# Sheet_CL-RMS-01.net
KiCad netlist of a schematic drawn in Altium Designer
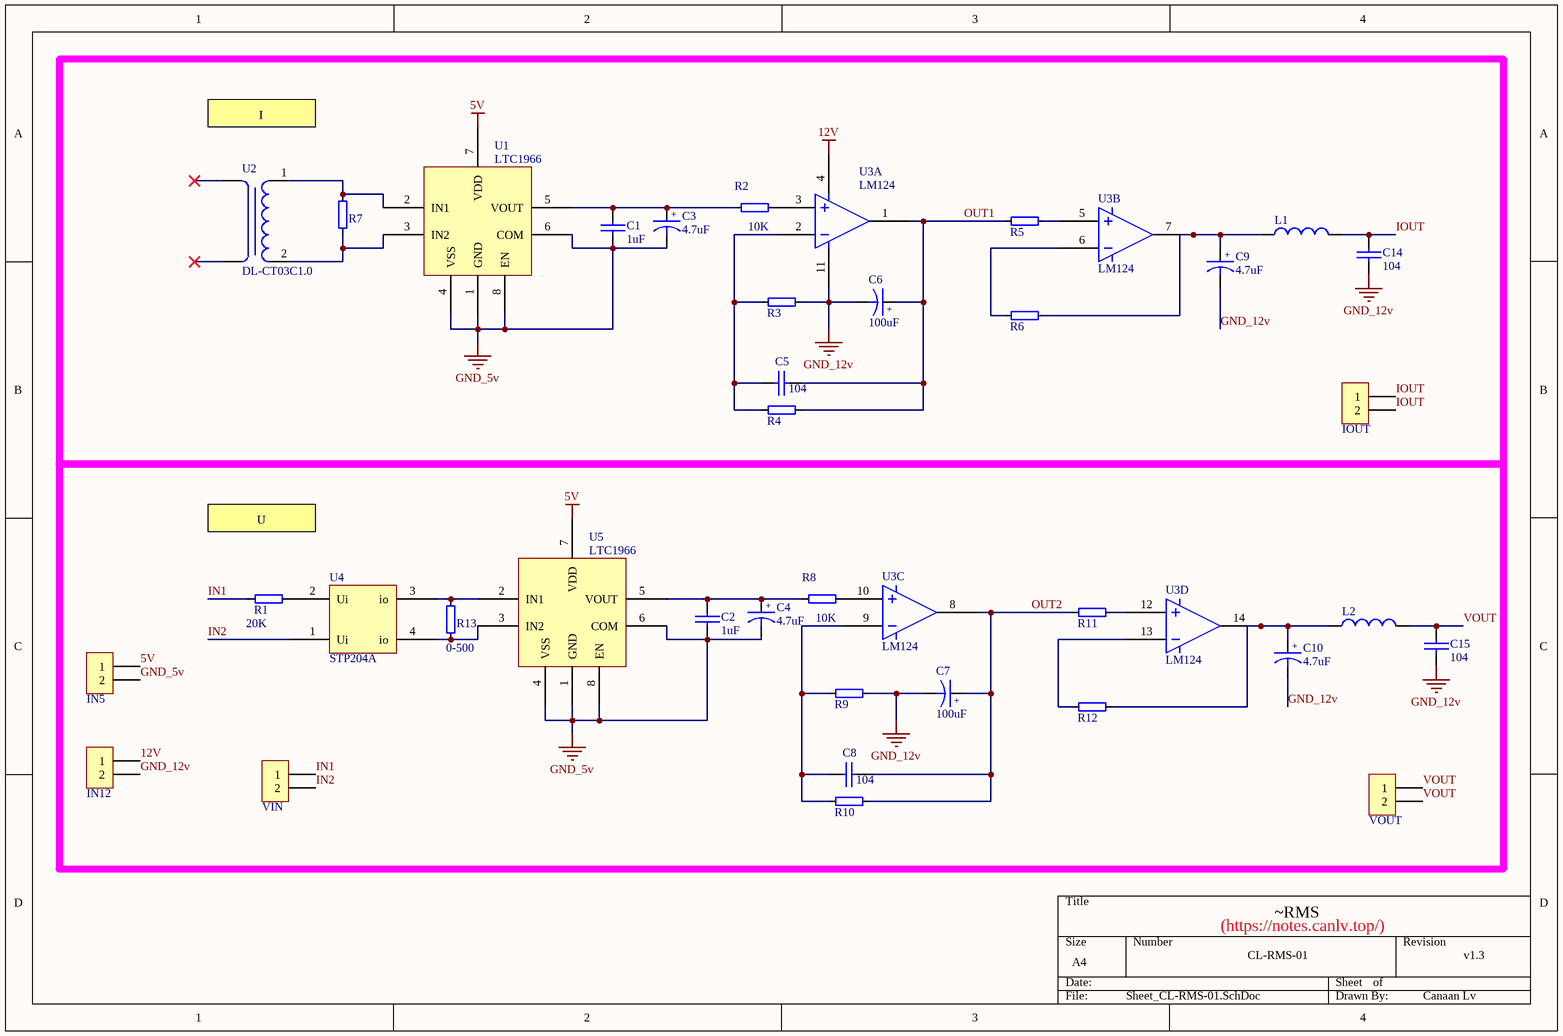
[diagram p0: Sheet_CL-RMS-01.SchDoc]

(export (version "E")
  (design (tool "Eeschema 10.0.6"))
  (components
    (comp (ref "C1")
      (value "普通电容")
      (footprint "C0805")
      (description "Capacitor")
      (fields (field (name "ALTIUM_UNNAMED_1") "1uF"))
      (libsource (lib "电容") (part "普通电容"))
    )
    (comp (ref "C2")
      (value "普通电容")
      (footprint "C0805")
      (description "Capacitor")
      (fields (field (name "ALTIUM_UNNAMED_1") "1uF"))
      (libsource (lib "电容") (part "普通电容"))
    )
    (comp (ref "C3")
      (value "电解电容")
      (footprint "CZ0.50/25V47U")
      (description "Capacitor")
      (fields (field (name "ALTIUM_UNNAMED_1") "4.7uF"))
      (libsource (lib "电容") (part "电解电容"))
    )
    (comp (ref "C4")
      (value "电解电容")
      (footprint "CZ0.50/25V47U")
      (description "Capacitor")
      (fields (field (name "ALTIUM_UNNAMED_1") "4.7uF"))
      (libsource (lib "电容") (part "电解电容"))
    )
    (comp (ref "C5")
      (value "普通电容")
      (footprint "C0805")
      (description "Capacitor")
      (fields (field (name "ALTIUM_UNNAMED_1") "104"))
      (libsource (lib "电容") (part "普通电容"))
    )
    (comp (ref "C6")
      (value "电解电容")
      (footprint "CZ0.50/25V47U")
      (description "Capacitor")
      (fields (field (name "ALTIUM_UNNAMED_1") "100uF"))
      (libsource (lib "电容") (part "电解电容"))
    )
    (comp (ref "C7")
      (value "电解电容")
      (footprint "CZ0.50/25V47U")
      (description "Capacitor")
      (fields (field (name "ALTIUM_UNNAMED_1") "100uF"))
      (libsource (lib "电容") (part "电解电容"))
    )
    (comp (ref "C8")
      (value "普通电容")
      (footprint "C0805")
      (description "Capacitor")
      (fields (field (name "ALTIUM_UNNAMED_1") "104"))
      (libsource (lib "电容") (part "普通电容"))
    )
    (comp (ref "C9")
      (value "电解电容")
      (footprint "CZ0.50/25V47U")
      (description "Capacitor")
      (fields (field (name "ALTIUM_UNNAMED_1") "4.7uF"))
      (libsource (lib "电容") (part "电解电容"))
    )
    (comp (ref "C10")
      (value "电解电容")
      (footprint "CZ0.50/25V47U")
      (description "Capacitor")
      (fields (field (name "ALTIUM_UNNAMED_1") "4.7uF"))
      (libsource (lib "电容") (part "电解电容"))
    )
    (comp (ref "C14")
      (value "普通电容")
      (footprint "C0805")
      (description "Capacitor")
      (fields (field (name "ALTIUM_UNNAMED_1") "104"))
      (libsource (lib "电容") (part "普通电容"))
    )
    (comp (ref "C15")
      (value "普通电容")
      (footprint "C0805")
      (description "Capacitor")
      (fields (field (name "ALTIUM_UNNAMED_1") "104"))
      (libsource (lib "电容") (part "普通电容"))
    )
    (comp (ref "IN5")
      (value "CON2")
      (footprint "P2")
      (description "Connector")
      (libsource (lib "插件") (part "CON2"))
    )
    (comp (ref "IN12")
      (value "CON2")
      (footprint "P2")
      (description "Connector")
      (libsource (lib "插件") (part "CON2"))
    )
    (comp (ref "IOUT")
      (value "CON2")
      (footprint "P2")
      (description "Connector")
      (libsource (lib "插件") (part "CON2"))
    )
    (comp (ref "L1") (value "~") (footprint "L1206") (libsource (lib "电感") (part "贴片电感")))
    (comp (ref "L2") (value "~") (footprint "L1206") (libsource (lib "电感") (part "贴片电感")))
    (comp (ref "R1")
      (value "RES")
      (footprint "W1")
      (fields (field (name "ALTIUM_UNNAMED_1") "20K"))
      (libsource (lib "电阻") (part "RES"))
    )
    (comp (ref "R2")
      (value "RES")
      (footprint "C0805")
      (fields (field (name "ALTIUM_UNNAMED_1") "10K"))
      (libsource (lib "电阻") (part "RES"))
    )
    (comp (ref "R3") (value "RES") (footprint "C0805") (libsource (lib "电阻") (part "RES")))
    (comp (ref "R4") (value "RES") (footprint "W1") (libsource (lib "电阻") (part "RES")))
    (comp (ref "R5") (value "RES") (footprint "C0805") (libsource (lib "电阻") (part "RES")))
    (comp (ref "R6") (value "RES") (footprint "C0805") (libsource (lib "电阻") (part "RES")))
    (comp (ref "R7") (value "RES") (footprint "W1") (libsource (lib "电阻") (part "RES")))
    (comp (ref "R8")
      (value "RES")
      (footprint "C0805")
      (fields (field (name "ALTIUM_UNNAMED_1") "10K"))
      (libsource (lib "电阻") (part "RES"))
    )
    (comp (ref "R9") (value "RES") (footprint "C0805") (libsource (lib "电阻") (part "RES")))
    (comp (ref "R10") (value "RES") (footprint "W1") (libsource (lib "电阻") (part "RES")))
    (comp (ref "R11") (value "RES") (footprint "C0805") (libsource (lib "电阻") (part "RES")))
    (comp (ref "R12") (value "RES") (footprint "C0805") (libsource (lib "电阻") (part "RES")))
    (comp (ref "R13")
      (value "RES")
      (footprint "W1")
      (fields (field (name "ALTIUM_UNNAMED_1") "0-500"))
      (libsource (lib "电阻") (part "RES"))
    )
    (comp (ref "U1") (value "LTC1966") (footprint "LTC1966") (libsource (lib "AD转换器件") (part "LTC1966")))
    (comp (ref "U2")
      (value "DL-CT03C1.0")
      (footprint "DL-CT03C1.0")
      (libsource (lib "感应元件") (part "DL-CT03C1.0"))
    )
    (comp (ref "U3") (value "LM124") (footprint "DIP-14") (libsource (lib "MISCESCH") (part "LM124")))
    (comp (ref "U4") (value "STP204A") (footprint "STP204A") (libsource (lib "感应元件") (part "STP204A")))
    (comp (ref "U5") (value "LTC1966") (footprint "LTC1966") (libsource (lib "AD转换器件") (part "LTC1966")))
    (comp (ref "VIN")
      (value "CON2")
      (footprint "P2")
      (description "Connector")
      (libsource (lib "插件") (part "CON2"))
    )
    (comp (ref "VOUT")
      (value "CON2")
      (footprint "P2")
      (description "Connector")
      (libsource (lib "插件") (part "CON2"))
    )
  )
  (nets
    (net (code "1") (name "/IN1") (class "Default")
      (node (ref "R1") (pin "1") (pinfunction "1_1") (pintype "passive"))
      (node (ref "VIN") (pin "1") (pinfunction "1_1") (pintype "passive"))
    )
    (net (code "2") (name "/IN2") (class "Default")
      (node (ref "U4") (pin "1") (pinfunction "Ui_1") (pintype "passive"))
      (node (ref "VIN") (pin "2") (pinfunction "2_2") (pintype "passive"))
    )
    (net (code "3") (name "/IOUT") (class "Default")
      (node (ref "C14") (pin "2") (pinfunction "2_2") (pintype "passive"))
      (node (ref "IOUT") (pin "1") (pinfunction "1_1") (pintype "passive"))
      (node (ref "IOUT") (pin "2") (pinfunction "2_2") (pintype "passive"))
      (node (ref "L1") (pin "2") (pinfunction "2_2") (pintype "passive"))
    )
    (net (code "4") (name "/OUT1") (class "Default")
      (node (ref "C5") (pin "2") (pinfunction "2_2") (pintype "passive"))
      (node (ref "C6") (pin "1") (pinfunction "1_1") (pintype "passive"))
      (node (ref "R4") (pin "2") (pinfunction "2_2") (pintype "passive"))
      (node (ref "R5") (pin "1") (pinfunction "1_1") (pintype "passive"))
      (node (ref "U3") (pin "1") (pintype "passive"))
    )
    (net (code "5") (name "/OUT2") (class "Default")
      (node (ref "C7") (pin "1") (pinfunction "1_1") (pintype "passive"))
      (node (ref "C8") (pin "2") (pinfunction "2_2") (pintype "passive"))
      (node (ref "R10") (pin "2") (pinfunction "2_2") (pintype "passive"))
      (node (ref "R11") (pin "1") (pinfunction "1_1") (pintype "passive"))
      (node (ref "U3") (pin "8") (pintype "passive"))
    )
    (net (code "6") (name "/VOUT") (class "Default")
      (node (ref "C15") (pin "2") (pinfunction "2_2") (pintype "passive"))
      (node (ref "L2") (pin "2") (pinfunction "2_2") (pintype "passive"))
      (node (ref "VOUT") (pin "1") (pinfunction "1_1") (pintype "passive"))
      (node (ref "VOUT") (pin "2") (pinfunction "2_2") (pintype "passive"))
    )
    (net (code "7") (name "5V") (class "Default")
      (node (ref "IN5") (pin "1") (pinfunction "1_1") (pintype "passive"))
      (node (ref "U1") (pin "7") (pinfunction "VDD_7") (pintype "passive"))
      (node (ref "U5") (pin "7") (pinfunction "VDD_7") (pintype "passive"))
    )
    (net (code "8") (name "12V") (class "Default")
      (node (ref "IN12") (pin "1") (pinfunction "1_1") (pintype "passive"))
      (node (ref "U3") (pin "4") (pintype "passive"))
    )
    (net (code "9") (name "GND_5v") (class "Default")
      (node (ref "C1") (pin "2") (pinfunction "2_2") (pintype "passive"))
      (node (ref "C2") (pin "2") (pinfunction "2_2") (pintype "passive"))
      (node (ref "C3") (pin "2") (pinfunction "2_2") (pintype "passive"))
      (node (ref "C4") (pin "2") (pinfunction "2_2") (pintype "passive"))
      (node (ref "IN5") (pin "2") (pinfunction "2_2") (pintype "passive"))
      (node (ref "U1") (pin "1") (pinfunction "GND_1") (pintype "passive"))
      (node (ref "U1") (pin "4") (pinfunction "VSS_4") (pintype "passive"))
      (node (ref "U1") (pin "6") (pinfunction "COM_6") (pintype "passive"))
      (node (ref "U1") (pin "8") (pinfunction "EN_8") (pintype "passive"))
      (node (ref "U5") (pin "1") (pinfunction "GND_1") (pintype "passive"))
      (node (ref "U5") (pin "4") (pinfunction "VSS_4") (pintype "passive"))
      (node (ref "U5") (pin "6") (pinfunction "COM_6") (pintype "passive"))
      (node (ref "U5") (pin "8") (pinfunction "EN_8") (pintype "passive"))
    )
    (net (code "10") (name "GND_12v") (class "Default")
      (node (ref "C10") (pin "2") (pinfunction "2_2") (pintype "passive"))
      (node (ref "C14") (pin "1") (pinfunction "1_1") (pintype "passive"))
      (node (ref "C15") (pin "1") (pinfunction "1_1") (pintype "passive"))
      (node (ref "C6") (pin "2") (pinfunction "2_2") (pintype "passive"))
      (node (ref "C7") (pin "2") (pinfunction "2_2") (pintype "passive"))
      (node (ref "C9") (pin "2") (pinfunction "2_2") (pintype "passive"))
      (node (ref "IN12") (pin "2") (pinfunction "2_2") (pintype "passive"))
      (node (ref "R3") (pin "2") (pinfunction "2_2") (pintype "passive"))
      (node (ref "R9") (pin "2") (pinfunction "2_2") (pintype "passive"))
      (node (ref "U3") (pin "11") (pintype "passive"))
    )
    (net (code "11") (name "Net-(C5-Pad1)") (class "Default")
      (node (ref "C5") (pin "1") (pinfunction "1_1") (pintype "passive"))
      (node (ref "R3") (pin "1") (pinfunction "1_1") (pintype "passive"))
      (node (ref "R4") (pin "1") (pinfunction "1_1") (pintype "passive"))
      (node (ref "U3") (pin "2") (pintype "passive"))
    )
    (net (code "12") (name "Net-(C8-Pad1)") (class "Default")
      (node (ref "C8") (pin "1") (pinfunction "1_1") (pintype "passive"))
      (node (ref "R10") (pin "1") (pinfunction "1_1") (pintype "passive"))
      (node (ref "R9") (pin "1") (pinfunction "1_1") (pintype "passive"))
      (node (ref "U3") (pin "9") (pintype "passive"))
    )
    (net (code "13") (name "Net-(C9-Pad1)") (class "Default")
      (node (ref "C9") (pin "1") (pinfunction "1_1") (pintype "passive"))
      (node (ref "L1") (pin "1") (pinfunction "1_1") (pintype "passive"))
      (node (ref "R6") (pin "2") (pinfunction "2_2") (pintype "passive"))
      (node (ref "U3") (pin "7") (pintype "passive"))
    )
    (net (code "14") (name "Net-(C10-Pad1)") (class "Default")
      (node (ref "C10") (pin "1") (pinfunction "1_1") (pintype "passive"))
      (node (ref "L2") (pin "1") (pinfunction "1_1") (pintype "passive"))
      (node (ref "R12") (pin "2") (pinfunction "2_2") (pintype "passive"))
      (node (ref "U3") (pin "14") (pintype "passive"))
    )
    (net (code "15") (name "Net-(R1-Pad2)") (class "Default")
      (node (ref "R1") (pin "2") (pinfunction "2_2") (pintype "passive"))
      (node (ref "U4") (pin "2") (pinfunction "Ui_2") (pintype "passive"))
    )
    (net (code "16") (name "Net-(R2-Pad2)") (class "Default")
      (node (ref "R2") (pin "2") (pinfunction "2_2") (pintype "passive"))
      (node (ref "U3") (pin "3") (pintype "passive"))
    )
    (net (code "17") (name "Net-(R5-Pad2)") (class "Default")
      (node (ref "R5") (pin "2") (pinfunction "2_2") (pintype "passive"))
      (node (ref "U3") (pin "5") (pintype "passive"))
    )
    (net (code "18") (name "Net-(R6-Pad1)") (class "Default")
      (node (ref "R6") (pin "1") (pinfunction "1_1") (pintype "passive"))
      (node (ref "U3") (pin "6") (pintype "passive"))
    )
    (net (code "19") (name "Net-(R8-Pad2)") (class "Default")
      (node (ref "R8") (pin "2") (pinfunction "2_2") (pintype "passive"))
      (node (ref "U3") (pin "10") (pintype "passive"))
    )
    (net (code "20") (name "Net-(R11-Pad2)") (class "Default")
      (node (ref "R11") (pin "2") (pinfunction "2_2") (pintype "passive"))
      (node (ref "U3") (pin "12") (pintype "passive"))
    )
    (net (code "21") (name "Net-(R12-Pad1)") (class "Default")
      (node (ref "R12") (pin "1") (pinfunction "1_1") (pintype "passive"))
      (node (ref "U3") (pin "13") (pintype "passive"))
    )
    (net (code "22") (name "Net-(U1-IN1)") (class "Default")
      (node (ref "R7") (pin "2") (pinfunction "2_2") (pintype "passive"))
      (node (ref "U1") (pin "2") (pinfunction "IN1_2") (pintype "passive"))
      (node (ref "U2") (pin "1") (pintype "passive"))
    )
    (net (code "23") (name "Net-(U1-IN2)") (class "Default")
      (node (ref "R7") (pin "1") (pinfunction "1_1") (pintype "passive"))
      (node (ref "U1") (pin "3") (pinfunction "IN2_3") (pintype "passive"))
      (node (ref "U2") (pin "2") (pintype "passive"))
    )
    (net (code "24") (name "Net-(U1-VOUT)") (class "Default")
      (node (ref "C1") (pin "1") (pinfunction "1_1") (pintype "passive"))
      (node (ref "C3") (pin "1") (pinfunction "1_1") (pintype "passive"))
      (node (ref "R2") (pin "1") (pinfunction "1_1") (pintype "passive"))
      (node (ref "U1") (pin "5") (pinfunction "VOUT_5") (pintype "passive"))
    )
    (net (code "25") (name "Net-(U5-IN1)") (class "Default")
      (node (ref "R13") (pin "2") (pinfunction "2_2") (pintype "passive"))
      (node (ref "U4") (pin "3") (pinfunction "io_3") (pintype "passive"))
      (node (ref "U5") (pin "2") (pinfunction "IN1_2") (pintype "passive"))
    )
    (net (code "26") (name "Net-(U5-IN2)") (class "Default")
      (node (ref "R13") (pin "1") (pinfunction "1_1") (pintype "passive"))
      (node (ref "U4") (pin "4") (pinfunction "io_4") (pintype "passive"))
      (node (ref "U5") (pin "3") (pinfunction "IN2_3") (pintype "passive"))
    )
    (net (code "27") (name "Net-(U5-VOUT)") (class "Default")
      (node (ref "C2") (pin "1") (pinfunction "1_1") (pintype "passive"))
      (node (ref "C4") (pin "1") (pinfunction "1_1") (pintype "passive"))
      (node (ref "R8") (pin "1") (pinfunction "1_1") (pintype "passive"))
      (node (ref "U5") (pin "5") (pinfunction "VOUT_5") (pintype "passive"))
    )
    (net (code "28") (name "unconnected-(U2-Pad0)") (class "Default")
      (node (ref "U2") (pin "0") (pintype "passive+no_connect"))
    )
    (net (code "29") (name "unconnected-(U2-Pad0)_1") (class "Default")
      (node (ref "U2") (pin "0") (pintype "passive+no_connect"))
    )
  )
)
